# Connector.net
KiCad netlist of a schematic drawn in Altium Designer
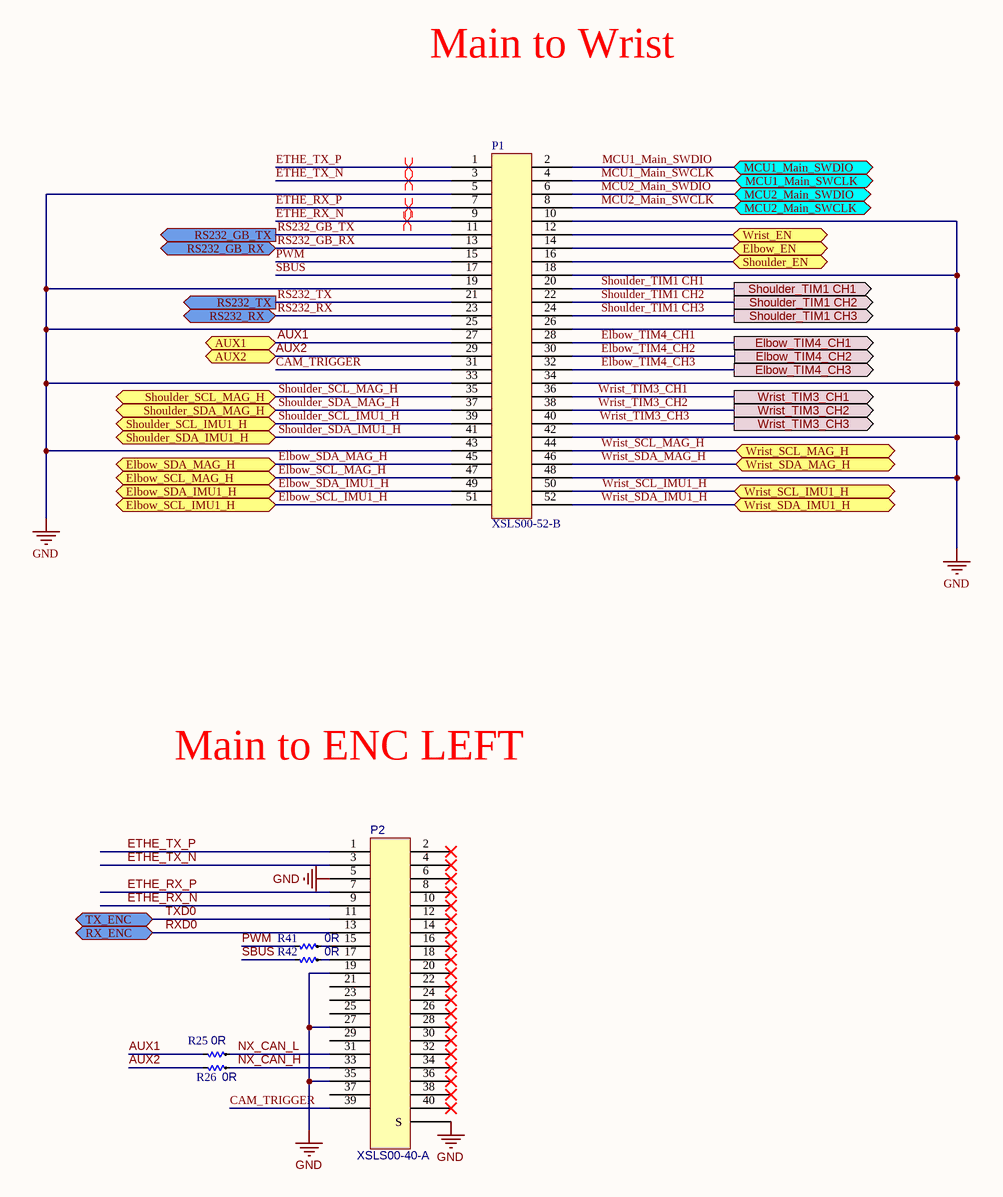
[diagram p0: Connector.SchDoc]

(export (version "E")
  (design (tool "Eeschema 10.0.6"))
  (components
    (comp (ref "P1")
      (value "XSLS00-52-B")
      (footprint "XSXL52")
      (libsource (lib "Hera_Sight_PixyU2") (part "XSLS00-52-B"))
    )
    (comp (ref "P2") (value "XSLS00-40-A") (footprint "XSXL40") (libsource (lib "RTR") (part "XSLS00-40-A")))
    (comp (ref "R25")
      (value "0R")
      (footprint "RES0402")
      (description "RES 0R 0402")
      (fields (field (name "MP") "RC0402JR-070RL") (field (name "TOLERANCE") "5%"))
      (libsource (lib "RTR (1)") (part "RES0402 0R"))
    )
    (comp (ref "R26")
      (value "0R")
      (footprint "RES0402")
      (description "RES 0R 0402")
      (fields (field (name "MP") "RC0402JR-070RL") (field (name "TOLERANCE") "5%"))
      (libsource (lib "RTR (1)") (part "RES0402 0R"))
    )
    (comp (ref "R41")
      (value "0R")
      (footprint "RES0402")
      (description "RES 0R 0402")
      (fields (field (name "MP") "RC0402JR-070RL") (field (name "TOLERANCE") "5%"))
      (libsource (lib "RTR (1)") (part "RES0402 0R"))
    )
    (comp (ref "R42")
      (value "0R")
      (footprint "RES0402")
      (description "RES 0R 0402")
      (fields (field (name "MP") "RC0402JR-070RL") (field (name "TOLERANCE") "5%"))
      (libsource (lib "RTR (1)") (part "RES0402 0R"))
    )
  )
  (nets
    (net (code "1") (name "/AUX1") (class "Default")
      (node (ref "P1") (pin "27") (pintype "passive"))
      (node (ref "R25") (pin "1") (pinfunction "1_1") (pintype "passive"))
    )
    (net (code "2") (name "/AUX2") (class "Default")
      (node (ref "P1") (pin "29") (pintype "passive"))
      (node (ref "R26") (pin "1") (pinfunction "1_1") (pintype "passive"))
    )
    (net (code "3") (name "/CAM_TRIGGER") (class "Default")
      (node (ref "P1") (pin "31") (pintype "passive"))
      (node (ref "P2") (pin "39") (pintype "passive"))
    )
    (net (code "4") (name "/ETHE_RX_N") (class "Default")
      (node (ref "P1") (pin "9") (pintype "passive"))
      (node (ref "P2") (pin "9") (pintype "passive"))
    )
    (net (code "5") (name "/ETHE_RX_P") (class "Default")
      (node (ref "P1") (pin "7") (pintype "passive"))
      (node (ref "P2") (pin "7") (pintype "passive"))
    )
    (net (code "6") (name "/ETHE_TX_N") (class "Default")
      (node (ref "P1") (pin "3") (pintype "passive"))
      (node (ref "P2") (pin "3") (pintype "passive"))
    )
    (net (code "7") (name "/ETHE_TX_P") (class "Default")
      (node (ref "P1") (pin "1") (pintype "passive"))
      (node (ref "P2") (pin "1") (pintype "passive"))
    )
    (net (code "8") (name "/Elbow_EN") (class "Default") (node (ref "P1") (pin "14") (pintype "passive")))
    (net (code "9") (name "/Elbow_SCL_IMU1_H") (class "Default")
      (node (ref "P1") (pin "51") (pintype "passive"))
    )
    (net (code "10") (name "/Elbow_SCL_MAG_H") (class "Default")
      (node (ref "P1") (pin "47") (pintype "passive"))
    )
    (net (code "11") (name "/Elbow_SDA_IMU1_H") (class "Default")
      (node (ref "P1") (pin "49") (pintype "passive"))
    )
    (net (code "12") (name "/Elbow_SDA_MAG_H") (class "Default")
      (node (ref "P1") (pin "45") (pintype "passive"))
    )
    (net (code "13") (name "/Elbow_TIM4_CH1") (class "Default")
      (node (ref "P1") (pin "28") (pintype "passive"))
    )
    (net (code "14") (name "/Elbow_TIM4_CH2") (class "Default")
      (node (ref "P1") (pin "30") (pintype "passive"))
    )
    (net (code "15") (name "/Elbow_TIM4_CH3") (class "Default")
      (node (ref "P1") (pin "32") (pintype "passive"))
    )
    (net (code "16") (name "/MCU1_Main_SWCLK") (class "Default")
      (node (ref "P1") (pin "4") (pintype "passive"))
    )
    (net (code "17") (name "/MCU1_Main_SWDIO") (class "Default")
      (node (ref "P1") (pin "2") (pintype "passive"))
    )
    (net (code "18") (name "/MCU2_Main_SWCLK") (class "Default")
      (node (ref "P1") (pin "8") (pintype "passive"))
    )
    (net (code "19") (name "/MCU2_Main_SWDIO") (class "Default")
      (node (ref "P1") (pin "6") (pintype "passive"))
    )
    (net (code "20") (name "/NX_CAN_H") (class "Default")
      (node (ref "P2") (pin "33") (pintype "passive"))
      (node (ref "R26") (pin "2") (pinfunction "2_2") (pintype "passive"))
    )
    (net (code "21") (name "/NX_CAN_L") (class "Default")
      (node (ref "P2") (pin "31") (pintype "passive"))
      (node (ref "R25") (pin "2") (pinfunction "2_2") (pintype "passive"))
    )
    (net (code "22") (name "/PWM") (class "Default")
      (node (ref "P1") (pin "15") (pintype "passive"))
      (node (ref "R41") (pin "1") (pinfunction "1_1") (pintype "passive"))
    )
    (net (code "23") (name "/RS232_GB_RX") (class "Default") (node (ref "P1") (pin "13") (pintype "passive")))
    (net (code "24") (name "/RS232_GB_TX") (class "Default") (node (ref "P1") (pin "11") (pintype "passive")))
    (net (code "25") (name "/RS232_RX") (class "Default") (node (ref "P1") (pin "23") (pintype "passive")))
    (net (code "26") (name "/RS232_TX") (class "Default") (node (ref "P1") (pin "21") (pintype "passive")))
    (net (code "27") (name "/RXD0") (class "Default") (node (ref "P2") (pin "13") (pintype "passive")))
    (net (code "28") (name "/SBUS") (class "Default")
      (node (ref "P1") (pin "17") (pintype "passive"))
      (node (ref "R42") (pin "1") (pinfunction "1_1") (pintype "passive"))
    )
    (net (code "29") (name "/Shoulder_EN") (class "Default") (node (ref "P1") (pin "16") (pintype "passive")))
    (net (code "30") (name "/Shoulder_SCL_IMU1_H") (class "Default")
      (node (ref "P1") (pin "39") (pintype "passive"))
    )
    (net (code "31") (name "/Shoulder_SCL_MAG_H") (class "Default")
      (node (ref "P1") (pin "35") (pintype "passive"))
    )
    (net (code "32") (name "/Shoulder_SDA_IMU1_H") (class "Default")
      (node (ref "P1") (pin "41") (pintype "passive"))
    )
    (net (code "33") (name "/Shoulder_SDA_MAG_H") (class "Default")
      (node (ref "P1") (pin "37") (pintype "passive"))
    )
    (net (code "34") (name "/Shoulder_TIM1 CH1") (class "Default")
      (node (ref "P1") (pin "20") (pintype "passive"))
    )
    (net (code "35") (name "/Shoulder_TIM1 CH2") (class "Default")
      (node (ref "P1") (pin "22") (pintype "passive"))
    )
    (net (code "36") (name "/Shoulder_TIM1 CH3") (class "Default")
      (node (ref "P1") (pin "24") (pintype "passive"))
    )
    (net (code "37") (name "/TXD0") (class "Default") (node (ref "P2") (pin "11") (pintype "passive")))
    (net (code "38") (name "/Wrist_EN") (class "Default") (node (ref "P1") (pin "12") (pintype "passive")))
    (net (code "39") (name "/Wrist_SCL_IMU1_H") (class "Default")
      (node (ref "P1") (pin "50") (pintype "passive"))
    )
    (net (code "40") (name "/Wrist_SCL_MAG_H") (class "Default")
      (node (ref "P1") (pin "44") (pintype "passive"))
    )
    (net (code "41") (name "/Wrist_SDA_IMU1_H") (class "Default")
      (node (ref "P1") (pin "52") (pintype "passive"))
    )
    (net (code "42") (name "/Wrist_SDA_MAG_H") (class "Default")
      (node (ref "P1") (pin "46") (pintype "passive"))
    )
    (net (code "43") (name "/Wrist_TIM3_CH1") (class "Default")
      (node (ref "P1") (pin "36") (pintype "passive"))
    )
    (net (code "44") (name "/Wrist_TIM3_CH2") (class "Default")
      (node (ref "P1") (pin "38") (pintype "passive"))
    )
    (net (code "45") (name "/Wrist_TIM3_CH3") (class "Default")
      (node (ref "P1") (pin "40") (pintype "passive"))
    )
    (net (code "46") (name "GND") (class "Default")
      (node (ref "P1") (pin "10") (pintype "passive"))
      (node (ref "P1") (pin "18") (pintype "passive"))
      (node (ref "P1") (pin "19") (pintype "passive"))
      (node (ref "P1") (pin "25") (pintype "passive"))
      (node (ref "P1") (pin "26") (pintype "passive"))
      (node (ref "P1") (pin "33") (pintype "passive"))
      (node (ref "P1") (pin "34") (pintype "passive"))
      (node (ref "P1") (pin "42") (pintype "passive"))
      (node (ref "P1") (pin "43") (pintype "passive"))
      (node (ref "P1") (pin "48") (pintype "passive"))
      (node (ref "P1") (pin "5") (pintype "passive"))
      (node (ref "P2") (pin "0") (pinfunction "S_0") (pintype "passive"))
      (node (ref "P2") (pin "19") (pintype "passive"))
      (node (ref "P2") (pin "27") (pintype "passive"))
      (node (ref "P2") (pin "35") (pintype "passive"))
      (node (ref "P2") (pin "5") (pintype "passive"))
    )
    (net (code "47") (name "Net-(P2-Pad15)") (class "Default")
      (node (ref "P2") (pin "15") (pintype "passive"))
      (node (ref "R41") (pin "2") (pinfunction "2_2") (pintype "passive"))
    )
    (net (code "48") (name "Net-(P2-Pad17)") (class "Default")
      (node (ref "P2") (pin "17") (pintype "passive"))
      (node (ref "R42") (pin "2") (pinfunction "2_2") (pintype "passive"))
    )
    (net (code "49") (name "unconnected-(P2-Pad2)") (class "Default")
      (node (ref "P2") (pin "2") (pintype "passive+no_connect"))
    )
    (net (code "50") (name "unconnected-(P2-Pad4)") (class "Default")
      (node (ref "P2") (pin "4") (pintype "passive+no_connect"))
    )
    (net (code "51") (name "unconnected-(P2-Pad6)") (class "Default")
      (node (ref "P2") (pin "6") (pintype "passive+no_connect"))
    )
    (net (code "52") (name "unconnected-(P2-Pad8)") (class "Default")
      (node (ref "P2") (pin "8") (pintype "passive+no_connect"))
    )
    (net (code "53") (name "unconnected-(P2-Pad10)") (class "Default")
      (node (ref "P2") (pin "10") (pintype "passive+no_connect"))
    )
    (net (code "54") (name "unconnected-(P2-Pad12)") (class "Default")
      (node (ref "P2") (pin "12") (pintype "passive+no_connect"))
    )
    (net (code "55") (name "unconnected-(P2-Pad14)") (class "Default")
      (node (ref "P2") (pin "14") (pintype "passive+no_connect"))
    )
    (net (code "56") (name "unconnected-(P2-Pad16)") (class "Default")
      (node (ref "P2") (pin "16") (pintype "passive+no_connect"))
    )
    (net (code "57") (name "unconnected-(P2-Pad18)") (class "Default")
      (node (ref "P2") (pin "18") (pintype "passive+no_connect"))
    )
    (net (code "58") (name "unconnected-(P2-Pad20)") (class "Default")
      (node (ref "P2") (pin "20") (pintype "passive+no_connect"))
    )
    (net (code "59") (name "unconnected-(P2-Pad21)") (class "Default")
      (node (ref "P2") (pin "21") (pintype "passive"))
    )
    (net (code "60") (name "unconnected-(P2-Pad22)") (class "Default")
      (node (ref "P2") (pin "22") (pintype "passive+no_connect"))
    )
    (net (code "61") (name "unconnected-(P2-Pad23)") (class "Default")
      (node (ref "P2") (pin "23") (pintype "passive"))
    )
    (net (code "62") (name "unconnected-(P2-Pad24)") (class "Default")
      (node (ref "P2") (pin "24") (pintype "passive+no_connect"))
    )
    (net (code "63") (name "unconnected-(P2-Pad25)") (class "Default")
      (node (ref "P2") (pin "25") (pintype "passive"))
    )
    (net (code "64") (name "unconnected-(P2-Pad26)") (class "Default")
      (node (ref "P2") (pin "26") (pintype "passive+no_connect"))
    )
    (net (code "65") (name "unconnected-(P2-Pad28)") (class "Default")
      (node (ref "P2") (pin "28") (pintype "passive+no_connect"))
    )
    (net (code "66") (name "unconnected-(P2-Pad29)") (class "Default")
      (node (ref "P2") (pin "29") (pintype "passive"))
    )
    (net (code "67") (name "unconnected-(P2-Pad30)") (class "Default")
      (node (ref "P2") (pin "30") (pintype "passive+no_connect"))
    )
    (net (code "68") (name "unconnected-(P2-Pad32)") (class "Default")
      (node (ref "P2") (pin "32") (pintype "passive+no_connect"))
    )
    (net (code "69") (name "unconnected-(P2-Pad34)") (class "Default")
      (node (ref "P2") (pin "34") (pintype "passive+no_connect"))
    )
    (net (code "70") (name "unconnected-(P2-Pad36)") (class "Default")
      (node (ref "P2") (pin "36") (pintype "passive+no_connect"))
    )
    (net (code "71") (name "unconnected-(P2-Pad37)") (class "Default")
      (node (ref "P2") (pin "37") (pintype "passive"))
    )
    (net (code "72") (name "unconnected-(P2-Pad38)") (class "Default")
      (node (ref "P2") (pin "38") (pintype "passive+no_connect"))
    )
    (net (code "73") (name "unconnected-(P2-Pad40)") (class "Default")
      (node (ref "P2") (pin "40") (pintype "passive+no_connect"))
    )
  )
)
